# 000_MCU.net
KiCad netlist of a schematic drawn in Altium Designer
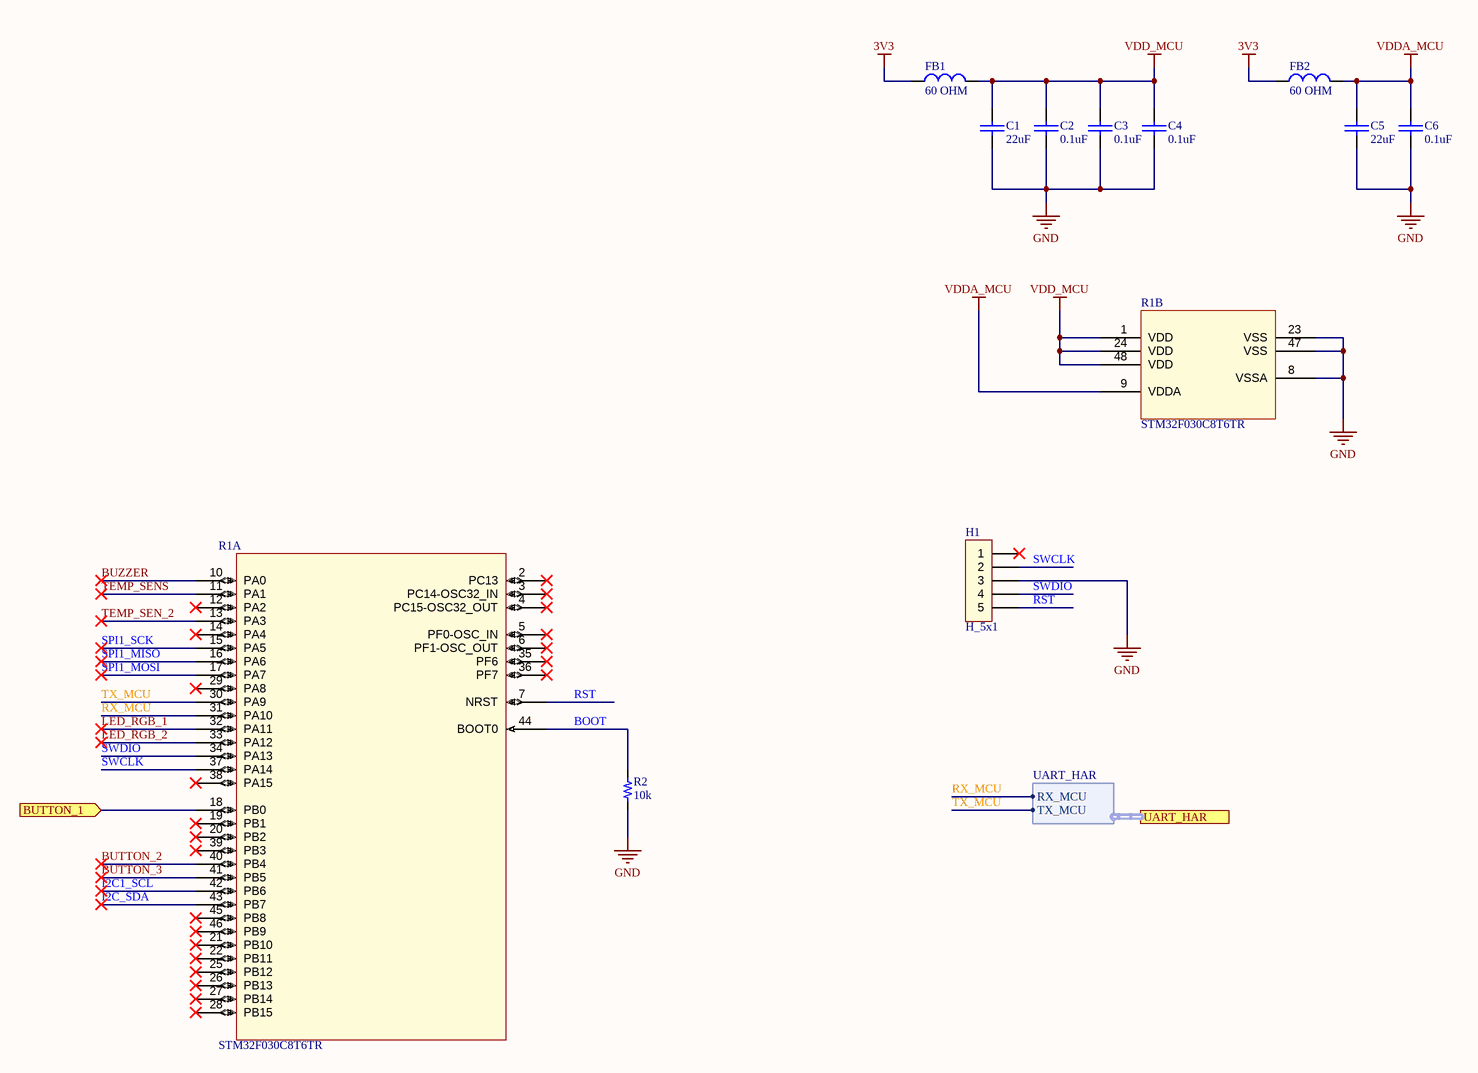
[diagram p0: 000_MCU.SchDoc]

(export (version "E")
  (design (tool "Eeschema 10.0.6"))
  (components
    (comp (ref "C1")
      (value "22uF")
      (footprint "0603_cap")
      (description "6.3V 22uF X5R ±20% 0805 Multilayer Ceramic Capacitors MLCC - SMD/SMT ROHS")
      (fields
        (field (name "MANUFACTURER") "Samsung Electro-Mechanics")
        (field (name "MANUFACTURER PART NUMBER") "CL21A226MQQNNNE")
      )
      (libsource (lib "shared_lib") (part "Cap_22uF_0805_6V3"))
    )
    (comp (ref "C2")
      (value "0.1uF")
      (footprint "0603_cap")
      (description "50V 100nF Y5V -20%~+80% 0603 Multilayer Ceramic Capacitors MLCC - SMD/SMT ROHS")
      (fields
        (field (name "MANUFACTURER") "Walsin Tech Corp")
        (field (name "MANUFACTURER PART NUMBER") "0603F104Z500CT")
      )
      (libsource (lib "shared_lib") (part "Cap_0.1uF_0603_50V"))
    )
    (comp (ref "C3")
      (value "0.1uF")
      (footprint "0603_cap")
      (description "50V 100nF Y5V -20%~+80% 0603 Multilayer Ceramic Capacitors MLCC - SMD/SMT ROHS")
      (fields
        (field (name "MANUFACTURER") "Walsin Tech Corp")
        (field (name "MANUFACTURER PART NUMBER") "0603F104Z500CT")
      )
      (libsource (lib "shared_lib") (part "Cap_0.1uF_0603_50V"))
    )
    (comp (ref "C4")
      (value "0.1uF")
      (footprint "0603_cap")
      (description "50V 100nF Y5V -20%~+80% 0603 Multilayer Ceramic Capacitors MLCC - SMD/SMT ROHS")
      (fields
        (field (name "MANUFACTURER") "Walsin Tech Corp")
        (field (name "MANUFACTURER PART NUMBER") "0603F104Z500CT")
      )
      (libsource (lib "shared_lib") (part "Cap_0.1uF_0603_50V"))
    )
    (comp (ref "C5")
      (value "22uF")
      (footprint "0603_cap")
      (description "6.3V 22uF X5R ±20% 0805 Multilayer Ceramic Capacitors MLCC - SMD/SMT ROHS")
      (fields
        (field (name "MANUFACTURER") "Samsung Electro-Mechanics")
        (field (name "MANUFACTURER PART NUMBER") "CL21A226MQQNNNE")
      )
      (libsource (lib "shared_lib") (part "Cap_22uF_0805_6V3"))
    )
    (comp (ref "C6")
      (value "0.1uF")
      (footprint "0603_cap")
      (description "50V 100nF Y5V -20%~+80% 0603 Multilayer Ceramic Capacitors MLCC - SMD/SMT ROHS")
      (fields
        (field (name "MANUFACTURER") "Walsin Tech Corp")
        (field (name "MANUFACTURER PART NUMBER") "0603F104Z500CT")
      )
      (libsource (lib "shared_lib") (part "Cap_0.1uF_0603_50V"))
    )
    (comp (ref "FB1")
      (value "60 OHM")
      (footprint "0603_fb")
      (description "2A 1 100mΩ 60Ω@100MHz ±25% 0603 Ferrite Beads ROHS")
      (fields
        (field (name "MANUFACTURER") "TAI-TECH")
        (field (name "MANUFACTURER PART NUMBER") "HCB1608KF-600T20")
      )
      (libsource (lib "shared_lib") (part "FB_60_0603_2A"))
    )
    (comp (ref "FB2")
      (value "60 OHM")
      (footprint "0603_fb")
      (description "2A 1 100mΩ 60Ω@100MHz ±25% 0603 Ferrite Beads ROHS")
      (fields
        (field (name "MANUFACTURER") "TAI-TECH")
        (field (name "MANUFACTURER PART NUMBER") "HCB1608KF-600T20")
      )
      (libsource (lib "shared_lib") (part "FB_60_0603_2A"))
    )
    (comp (ref "H1")
      (value "H_5x1")
      (footprint "H_5x1_TH_100mil")
      (description "Debugging male pin")
      (fields (field (name "LAST MODIFIED BY") "C-A.Serna.A"))
      (libsource (lib "Connectors") (part "H_Male_5x1_TH_100mil"))
    )
    (comp (ref "R1")
      (value "STM32F030C8T6TR")
      (footprint "LQFP48_7x7mm")
      (description "IC MCU 32BIT 64KB FLASH 48LQFP")
      (fields (field (name "MANUFACTURER") "STMicroelectronics"))
      (libsource (lib "shared_lib") (part "IC_STM32F030C8T6TR_LQFP48_7x7MM"))
    )
    (comp (ref "R2")
      (value "10k")
      (footprint "0603_res")
      (description "RES SMD 10k OHM 5% 1/10W 0603")
      (fields (field (name "MANUFACTURER") "FOJAN") (field (name "MANUFACTURER PART NUMBER") "FRC0603J103TS"))
      (libsource (lib "shared_lib") (part "Res_10k_0603_1/10W"))
    )
  )
  (nets
    (net (code "2") (name "/BOOT") (class "Default")
      (node (ref "R1") (pin "44") (pinfunction "BOOT0_44") (pintype "input"))
      (node (ref "R2") (pin "2") (pinfunction "2_2") (pintype "passive"))
    )
    (net (code "3") (name "/BUTTON_1") (class "Default")
      (node (ref "R1") (pin "18") (pinfunction "PB0_18") (pintype "bidirectional"))
    )
    (net (code "4") (name "/BUTTON_2") (class "Default")
      (node (ref "R1") (pin "40") (pinfunction "PB4_40") (pintype "bidirectional+no_connect"))
    )
    (net (code "5") (name "/BUTTON_3") (class "Default")
      (node (ref "R1") (pin "41") (pinfunction "PB5_41") (pintype "bidirectional+no_connect"))
    )
    (net (code "6") (name "/BUZZER") (class "Default")
      (node (ref "R1") (pin "10") (pinfunction "PA0_10") (pintype "bidirectional+no_connect"))
    )
    (net (code "7") (name "/I2C1_SCL") (class "Default")
      (node (ref "R1") (pin "42") (pinfunction "PB6_42") (pintype "bidirectional+no_connect"))
    )
    (net (code "8") (name "/I2C_SDA") (class "Default")
      (node (ref "R1") (pin "43") (pinfunction "PB7_43") (pintype "bidirectional+no_connect"))
    )
    (net (code "9") (name "/LED_RGB_1") (class "Default")
      (node (ref "R1") (pin "32") (pinfunction "PA11_32") (pintype "bidirectional+no_connect"))
    )
    (net (code "10") (name "/LED_RGB_2") (class "Default")
      (node (ref "R1") (pin "33") (pinfunction "PA12_33") (pintype "bidirectional+no_connect"))
    )
    (net (code "11") (name "/RST") (class "Default")
      (node (ref "H1") (pin "5") (pinfunction "5_5") (pintype "passive"))
      (node (ref "R1") (pin "7") (pinfunction "NRST_7") (pintype "bidirectional"))
    )
    (net (code "12") (name "/RX_MCU") (class "Default")
      (node (ref "R1") (pin "31") (pinfunction "PA10_31") (pintype "bidirectional"))
    )
    (net (code "13") (name "/SPI1_MISO") (class "Default")
      (node (ref "R1") (pin "16") (pinfunction "PA6_16") (pintype "bidirectional+no_connect"))
    )
    (net (code "14") (name "/SPI1_MOSI") (class "Default")
      (node (ref "R1") (pin "17") (pinfunction "PA7_17") (pintype "bidirectional+no_connect"))
    )
    (net (code "15") (name "/SPI1_SCK") (class "Default")
      (node (ref "R1") (pin "15") (pinfunction "PA5_15") (pintype "bidirectional+no_connect"))
    )
    (net (code "16") (name "/SWCLK") (class "Default")
      (node (ref "H1") (pin "2") (pinfunction "2_2") (pintype "passive"))
      (node (ref "R1") (pin "37") (pinfunction "PA14_37") (pintype "bidirectional"))
    )
    (net (code "17") (name "/SWDIO") (class "Default")
      (node (ref "H1") (pin "4") (pinfunction "4_4") (pintype "passive"))
      (node (ref "R1") (pin "34") (pinfunction "PA13_34") (pintype "bidirectional"))
    )
    (net (code "18") (name "/TEMP_SENS") (class "Default")
      (node (ref "R1") (pin "11") (pinfunction "PA1_11") (pintype "bidirectional+no_connect"))
    )
    (net (code "19") (name "/TEMP_SEN_2") (class "Default")
      (node (ref "R1") (pin "13") (pinfunction "PA3_13") (pintype "bidirectional+no_connect"))
    )
    (net (code "20") (name "/TX_MCU") (class "Default")
      (node (ref "R1") (pin "30") (pinfunction "PA9_30") (pintype "bidirectional"))
    )
    (net (code "22") (name "3V3") (class "Default")
      (node (ref "FB1") (pin "1") (pinfunction "1_1") (pintype "passive"))
      (node (ref "FB2") (pin "1") (pinfunction "1_1") (pintype "passive"))
    )
    (net (code "23") (name "GND") (class "Default")
      (node (ref "C1") (pin "2") (pinfunction "2_2") (pintype "passive"))
      (node (ref "C2") (pin "2") (pinfunction "2_2") (pintype "passive"))
      (node (ref "C3") (pin "2") (pinfunction "2_2") (pintype "passive"))
      (node (ref "C4") (pin "2") (pinfunction "2_2") (pintype "passive"))
      (node (ref "C5") (pin "2") (pinfunction "2_2") (pintype "passive"))
      (node (ref "C6") (pin "2") (pinfunction "2_2") (pintype "passive"))
      (node (ref "H1") (pin "3") (pinfunction "3_3") (pintype "passive"))
      (node (ref "R1") (pin "23") (pinfunction "VSS_23") (pintype "power_in"))
      (node (ref "R1") (pin "47") (pinfunction "VSS_47") (pintype "power_in"))
      (node (ref "R1") (pin "8") (pinfunction "VSSA_8") (pintype "power_in"))
      (node (ref "R2") (pin "1") (pinfunction "1_1") (pintype "passive"))
    )
    (net (code "24") (name "VDDA_MCU") (class "Default")
      (node (ref "C5") (pin "1") (pinfunction "1_1") (pintype "passive"))
      (node (ref "C6") (pin "1") (pinfunction "1_1") (pintype "passive"))
      (node (ref "FB2") (pin "2") (pinfunction "2_2") (pintype "passive"))
      (node (ref "R1") (pin "9") (pinfunction "VDDA_9") (pintype "power_in"))
    )
    (net (code "25") (name "VDD_MCU") (class "Default")
      (node (ref "C1") (pin "1") (pinfunction "1_1") (pintype "passive"))
      (node (ref "C2") (pin "1") (pinfunction "1_1") (pintype "passive"))
      (node (ref "C3") (pin "1") (pinfunction "1_1") (pintype "passive"))
      (node (ref "C4") (pin "1") (pinfunction "1_1") (pintype "passive"))
      (node (ref "FB1") (pin "2") (pinfunction "2_2") (pintype "passive"))
      (node (ref "R1") (pin "1") (pinfunction "VDD_1") (pintype "power_in"))
      (node (ref "R1") (pin "24") (pinfunction "VDD_24") (pintype "power_in"))
      (node (ref "R1") (pin "48") (pinfunction "VDD_48") (pintype "power_in"))
    )
    (net (code "26") (name "unconnected-(H1-Pad1)") (class "Default")
      (node (ref "H1") (pin "1") (pinfunction "1_1") (pintype "passive+no_connect"))
    )
    (net (code "27") (name "unconnected-(R1A-PA2-Pad12)") (class "Default")
      (node (ref "R1") (pin "12") (pinfunction "PA2_12") (pintype "bidirectional+no_connect"))
    )
    (net (code "28") (name "unconnected-(R1A-PA4-Pad14)") (class "Default")
      (node (ref "R1") (pin "14") (pinfunction "PA4_14") (pintype "bidirectional+no_connect"))
    )
    (net (code "29") (name "unconnected-(R1A-PA8-Pad29)") (class "Default")
      (node (ref "R1") (pin "29") (pinfunction "PA8_29") (pintype "bidirectional+no_connect"))
    )
    (net (code "30") (name "unconnected-(R1A-PA15-Pad38)") (class "Default")
      (node (ref "R1") (pin "38") (pinfunction "PA15_38") (pintype "bidirectional+no_connect"))
    )
    (net (code "31") (name "unconnected-(R1A-PB1-Pad19)") (class "Default")
      (node (ref "R1") (pin "19") (pinfunction "PB1_19") (pintype "bidirectional+no_connect"))
    )
    (net (code "32") (name "unconnected-(R1A-PB2-Pad20)") (class "Default")
      (node (ref "R1") (pin "20") (pinfunction "PB2_20") (pintype "bidirectional+no_connect"))
    )
    (net (code "33") (name "unconnected-(R1A-PB3-Pad39)") (class "Default")
      (node (ref "R1") (pin "39") (pinfunction "PB3_39") (pintype "bidirectional+no_connect"))
    )
    (net (code "34") (name "unconnected-(R1A-PB8-Pad45)") (class "Default")
      (node (ref "R1") (pin "45") (pinfunction "PB8_45") (pintype "bidirectional+no_connect"))
    )
    (net (code "35") (name "unconnected-(R1A-PB9-Pad46)") (class "Default")
      (node (ref "R1") (pin "46") (pinfunction "PB9_46") (pintype "bidirectional+no_connect"))
    )
    (net (code "36") (name "unconnected-(R1A-PB10-Pad21)") (class "Default")
      (node (ref "R1") (pin "21") (pinfunction "PB10_21") (pintype "bidirectional+no_connect"))
    )
    (net (code "37") (name "unconnected-(R1A-PB11-Pad22)") (class "Default")
      (node (ref "R1") (pin "22") (pinfunction "PB11_22") (pintype "bidirectional+no_connect"))
    )
    (net (code "38") (name "unconnected-(R1A-PB12-Pad25)") (class "Default")
      (node (ref "R1") (pin "25") (pinfunction "PB12_25") (pintype "bidirectional+no_connect"))
    )
    (net (code "39") (name "unconnected-(R1A-PB13-Pad26)") (class "Default")
      (node (ref "R1") (pin "26") (pinfunction "PB13_26") (pintype "bidirectional+no_connect"))
    )
    (net (code "40") (name "unconnected-(R1A-PB14-Pad27)") (class "Default")
      (node (ref "R1") (pin "27") (pinfunction "PB14_27") (pintype "bidirectional+no_connect"))
    )
    (net (code "41") (name "unconnected-(R1A-PB15-Pad28)") (class "Default")
      (node (ref "R1") (pin "28") (pinfunction "PB15_28") (pintype "bidirectional+no_connect"))
    )
    (net (code "42") (name "unconnected-(R1A-PC13-Pad2)") (class "Default")
      (node (ref "R1") (pin "2") (pinfunction "PC13_2") (pintype "bidirectional+no_connect"))
    )
    (net (code "43") (name "unconnected-(R1A-PC14-OSC32_IN-Pad3)") (class "Default")
      (node (ref "R1") (pin "3") (pinfunction "PC14-OSC32_IN_3") (pintype "bidirectional+no_connect"))
    )
    (net (code "44") (name "unconnected-(R1A-PC15-OSC32_OUT-Pad4)") (class "Default")
      (node (ref "R1") (pin "4") (pinfunction "PC15-OSC32_OUT_4") (pintype "bidirectional+no_connect"))
    )
    (net (code "45") (name "unconnected-(R1A-PF0-OSC_IN-Pad5)") (class "Default")
      (node (ref "R1") (pin "5") (pinfunction "PF0-OSC_IN_5") (pintype "bidirectional+no_connect"))
    )
    (net (code "46") (name "unconnected-(R1A-PF1-OSC_OUT-Pad6)") (class "Default")
      (node (ref "R1") (pin "6") (pinfunction "PF1-OSC_OUT_6") (pintype "bidirectional+no_connect"))
    )
    (net (code "47") (name "unconnected-(R1A-PF6-Pad35)") (class "Default")
      (node (ref "R1") (pin "35") (pinfunction "PF6_35") (pintype "bidirectional+no_connect"))
    )
    (net (code "48") (name "unconnected-(R1A-PF7-Pad36)") (class "Default")
      (node (ref "R1") (pin "36") (pinfunction "PF7_36") (pintype "bidirectional+no_connect"))
    )
  )
)
